# ColourDEV.net
KiCad netlist of a schematic drawn in EAGLE
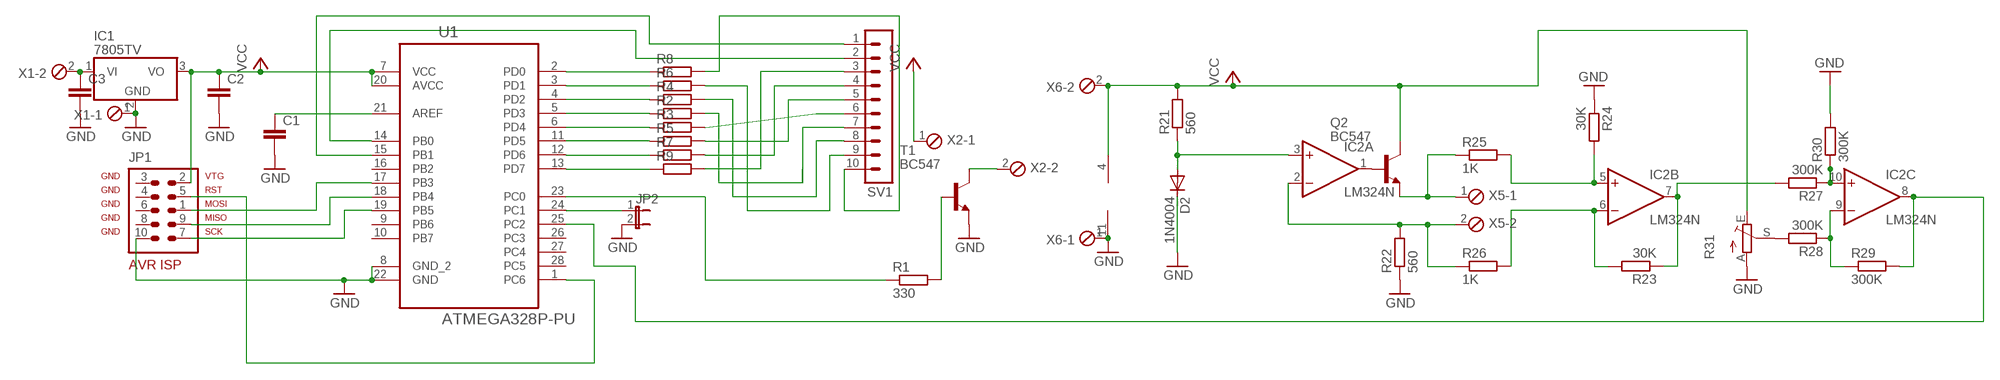
[diagram p0: schematic, sheet 1]

(export (version "E")
  (design (tool "Eeschema 10.0.6"))
  (components
    (comp (ref "C1")
      (value "C-EU050-075X075")
      (footprint "eagle-import:C050-075X075")
      (libsource (lib "eagle-import") (part "C-EU050-075X075"))
    )
    (comp (ref "C2")
      (value "C-EU050-025X075")
      (footprint "eagle-import:C050-025X075")
      (libsource (lib "eagle-import") (part "resistor_348_C-EU050-025X075"))
    )
    (comp (ref "C3")
      (value "C-EU050-025X075")
      (footprint "eagle-import:C050-025X075")
      (libsource (lib "eagle-import") (part "resistor_348_C-EU050-025X075"))
    )
    (comp (ref "D2")
      (value "1N4004")
      (footprint "eagle-import:DO41-10")
      (libsource (lib "eagle-import") (part "1N4004"))
    )
    (comp (ref "IC1")
      (value "7805TV")
      (footprint "eagle-import:TO220V")
      (libsource (lib "eagle-import") (part "78TV05"))
    )
    (comp (ref "IC2")
      (value "LM324N")
      (footprint "eagle-import:DIL14")
      (libsource (lib "eagle-import") (part "LM324N"))
    )
    (comp (ref "JP1")
      (value "AVR-ISP-10")
      (footprint "eagle-import:AVR-ISP-10")
      (libsource (lib "eagle-import") (part "AVR-ISP-10"))
    )
    (comp (ref "JP2")
      (value "JP1E")
      (footprint "eagle-import:JP1")
      (libsource (lib "eagle-import") (part "JP1E"))
    )
    (comp (ref "Q2")
      (value "BC547")
      (footprint "eagle-import:TO92")
      (libsource (lib "eagle-import") (part "BC547"))
    )
    (comp (ref "R1")
      (value "330")
      (footprint "eagle-import:M1206")
      (libsource (lib "eagle-import") (part "resistor_348_R-EU_M1206"))
    )
    (comp (ref "R2")
      (value "R-EU_M1206")
      (footprint "eagle-import:M1206")
      (libsource (lib "eagle-import") (part "resistor_348_R-EU_M1206"))
    )
    (comp (ref "R3")
      (value "R-EU_M1206")
      (footprint "eagle-import:M1206")
      (libsource (lib "eagle-import") (part "resistor_348_R-EU_M1206"))
    )
    (comp (ref "R4")
      (value "R-EU_M1206")
      (footprint "eagle-import:M1206")
      (libsource (lib "eagle-import") (part "resistor_348_R-EU_M1206"))
    )
    (comp (ref "R5")
      (value "R-EU_M1206")
      (footprint "eagle-import:M1206")
      (libsource (lib "eagle-import") (part "resistor_348_R-EU_M1206"))
    )
    (comp (ref "R6")
      (value "R-EU_M1206")
      (footprint "eagle-import:M1206")
      (libsource (lib "eagle-import") (part "resistor_348_R-EU_M1206"))
    )
    (comp (ref "R7")
      (value "R-EU_M1206")
      (footprint "eagle-import:M1206")
      (libsource (lib "eagle-import") (part "resistor_348_R-EU_M1206"))
    )
    (comp (ref "R8")
      (value "R-EU_M1206")
      (footprint "eagle-import:M1206")
      (libsource (lib "eagle-import") (part "resistor_348_R-EU_M1206"))
    )
    (comp (ref "R9")
      (value "R-EU_M1206")
      (footprint "eagle-import:M1206")
      (libsource (lib "eagle-import") (part "resistor_348_R-EU_M1206"))
    )
    (comp (ref "R21")
      (value "560")
      (footprint "eagle-import:M1206")
      (libsource (lib "eagle-import") (part "R-EU_M1206"))
    )
    (comp (ref "R22")
      (value "560")
      (footprint "eagle-import:M1206")
      (libsource (lib "eagle-import") (part "R-EU_M1206"))
    )
    (comp (ref "R23")
      (value "30K")
      (footprint "eagle-import:M1206")
      (libsource (lib "eagle-import") (part "R-EU_M1206"))
    )
    (comp (ref "R24")
      (value "30K")
      (footprint "eagle-import:M1206")
      (libsource (lib "eagle-import") (part "R-EU_M1206"))
    )
    (comp (ref "R25")
      (value "1K")
      (footprint "eagle-import:M1206")
      (libsource (lib "eagle-import") (part "R-EU_M1206"))
    )
    (comp (ref "R26")
      (value "1K")
      (footprint "eagle-import:M1206")
      (libsource (lib "eagle-import") (part "R-EU_M1206"))
    )
    (comp (ref "R27")
      (value "300K")
      (footprint "eagle-import:M1206")
      (libsource (lib "eagle-import") (part "R-EU_M1206"))
    )
    (comp (ref "R28")
      (value "300K")
      (footprint "eagle-import:M1206")
      (libsource (lib "eagle-import") (part "R-EU_M1206"))
    )
    (comp (ref "R29")
      (value "300K")
      (footprint "eagle-import:M1206")
      (libsource (lib "eagle-import") (part "R-EU_M1206"))
    )
    (comp (ref "R30")
      (value "300K")
      (footprint "eagle-import:M1206")
      (libsource (lib "eagle-import") (part "R-EU_M1206"))
    )
    (comp (ref "R31")
      (value "TRIM_EU-LI10")
      (footprint "eagle-import:LI10")
      (libsource (lib "eagle-import") (part "TRIM_EU-LI10"))
    )
    (comp (ref "SV1")
      (value "MA10-1")
      (footprint "eagle-import:MA10-1")
      (libsource (lib "eagle-import") (part "MA10-1"))
    )
    (comp (ref "T1")
      (value "BC547")
      (footprint "eagle-import:TO92")
      (libsource (lib "eagle-import") (part "transistor_402_BC547"))
    )
    (comp (ref "U1")
      (value "ATMEGA328P-PU")
      (footprint "eagle-import:DIP254P762X457-28")
      (libsource (lib "eagle-import") (part "ATMEGA328P-PU"))
    )
    (comp (ref "X1")
      (value "MPT2")
      (footprint "eagle-import:2POL254")
      (libsource (lib "eagle-import") (part "MPT2"))
    )
    (comp (ref "X2")
      (value "MPT2")
      (footprint "eagle-import:2POL254")
      (libsource (lib "eagle-import") (part "MPT2"))
    )
    (comp (ref "X5")
      (value "MPT2")
      (footprint "eagle-import:2POL254")
      (libsource (lib "eagle-import") (part "MPT2"))
    )
    (comp (ref "X6")
      (value "MPT2")
      (footprint "eagle-import:2POL254")
      (libsource (lib "eagle-import") (part "MPT2"))
    )
  )
  (nets
    (net (code "1") (name "GND") (class "Default")
      (node (ref "C1") (pin "2") (pinfunction "2_2") (pintype "passive"))
      (node (ref "C2") (pin "2") (pinfunction "2_2") (pintype "passive"))
      (node (ref "C3") (pin "2") (pinfunction "2_2") (pintype "passive"))
      (node (ref "D2") (pin "C") (pinfunction "C_C") (pintype "passive"))
      (node (ref "IC1") (pin "2") (pinfunction "GND_2") (pintype "passive"))
      (node (ref "IC2") (pin "11") (pinfunction "V-_11") (pintype "power_in"))
      (node (ref "JP1") (pin "10") (pinfunction "10_10") (pintype "passive"))
      (node (ref "JP2") (pin "2") (pinfunction "2_2") (pintype "passive"))
      (node (ref "R22") (pin "1") (pinfunction "1_1") (pintype "passive"))
      (node (ref "R24") (pin "1") (pinfunction "1_1") (pintype "passive"))
      (node (ref "R30") (pin "2") (pinfunction "2_2") (pintype "passive"))
      (node (ref "R31") (pin "A") (pinfunction "A_A") (pintype "passive"))
      (node (ref "T1") (pin "1") (pinfunction "E_1") (pintype "passive"))
      (node (ref "U1") (pin "22") (pinfunction "GND_22") (pintype "passive"))
      (node (ref "U1") (pin "8") (pinfunction "GND_2_8") (pintype "passive"))
      (node (ref "X1") (pin "1") (pinfunction "1_1") (pintype "passive"))
      (node (ref "X6") (pin "1") (pinfunction "1_1") (pintype "passive"))
    )
    (net (code "2") (name "Net-(IC1-VI)") (class "Default")
      (node (ref "C3") (pin "1") (pinfunction "1_1") (pintype "passive"))
      (node (ref "IC1") (pin "1") (pinfunction "VI_1") (pintype "input"))
      (node (ref "X1") (pin "2") (pinfunction "1_2") (pintype "passive"))
    )
    (net (code "3") (name "Net-(IC2A-+IN)") (class "Default")
      (node (ref "D2") (pin "A") (pinfunction "A_A") (pintype "passive"))
      (node (ref "IC2") (pin "3") (pinfunction "+IN_3") (pintype "input"))
      (node (ref "R21") (pin "1") (pinfunction "1_1") (pintype "passive"))
    )
    (net (code "4") (name "Net-(IC2A--IN)") (class "Default")
      (node (ref "IC2") (pin "2") (pinfunction "-IN_2") (pintype "input"))
      (node (ref "R22") (pin "2") (pinfunction "2_2") (pintype "passive"))
      (node (ref "R26") (pin "1") (pinfunction "1_1") (pintype "passive"))
      (node (ref "X5") (pin "2") (pinfunction "1_2") (pintype "passive"))
    )
    (net (code "5") (name "Net-(IC2A-OUT)") (class "Default")
      (node (ref "IC2") (pin "1") (pinfunction "OUT_1") (pintype "output"))
      (node (ref "Q2") (pin "2") (pinfunction "B_2") (pintype "passive"))
    )
    (net (code "6") (name "Net-(IC2B-+IN)") (class "Default")
      (node (ref "IC2") (pin "5") (pinfunction "+IN_5") (pintype "input"))
      (node (ref "R24") (pin "2") (pinfunction "2_2") (pintype "passive"))
      (node (ref "R25") (pin "2") (pinfunction "2_2") (pintype "passive"))
    )
    (net (code "7") (name "Net-(IC2B--IN)") (class "Default")
      (node (ref "IC2") (pin "6") (pinfunction "-IN_6") (pintype "input"))
      (node (ref "R23") (pin "2") (pinfunction "2_2") (pintype "passive"))
      (node (ref "R26") (pin "2") (pinfunction "2_2") (pintype "passive"))
    )
    (net (code "8") (name "Net-(IC2B-OUT)") (class "Default")
      (node (ref "IC2") (pin "7") (pinfunction "OUT_7") (pintype "output"))
      (node (ref "R23") (pin "1") (pinfunction "1_1") (pintype "passive"))
      (node (ref "R27") (pin "2") (pinfunction "2_2") (pintype "passive"))
    )
    (net (code "9") (name "Net-(IC2C-+IN)") (class "Default")
      (node (ref "IC2") (pin "10") (pinfunction "+IN_10") (pintype "input"))
      (node (ref "R27") (pin "1") (pinfunction "1_1") (pintype "passive"))
      (node (ref "R30") (pin "1") (pinfunction "1_1") (pintype "passive"))
    )
    (net (code "10") (name "Net-(IC2C--IN)") (class "Default")
      (node (ref "IC2") (pin "9") (pinfunction "-IN_9") (pintype "input"))
      (node (ref "R28") (pin "1") (pinfunction "1_1") (pintype "passive"))
      (node (ref "R29") (pin "1") (pinfunction "1_1") (pintype "passive"))
    )
    (net (code "11") (name "Net-(IC2C-OUT)") (class "Default")
      (node (ref "IC2") (pin "8") (pinfunction "OUT_8") (pintype "output"))
      (node (ref "R29") (pin "2") (pinfunction "2_2") (pintype "passive"))
      (node (ref "U1") (pin "25") (pinfunction "PC2_25") (pintype "bidirectional"))
    )
    (net (code "12") (name "Net-(Q2-E)") (class "Default")
      (node (ref "Q2") (pin "1") (pinfunction "E_1") (pintype "passive"))
      (node (ref "R25") (pin "1") (pinfunction "1_1") (pintype "passive"))
      (node (ref "X5") (pin "1") (pinfunction "1_1") (pintype "passive"))
    )
    (net (code "13") (name "Net-(R2-Pad2)") (class "Default")
      (node (ref "R2") (pin "2") (pinfunction "2_2") (pintype "passive"))
      (node (ref "SV1") (pin "7") (pinfunction "7_7") (pintype "passive"))
    )
    (net (code "14") (name "Net-(R3-Pad2)") (class "Default")
      (node (ref "R3") (pin "2") (pinfunction "2_2") (pintype "passive"))
      (node (ref "SV1") (pin "6") (pinfunction "6_6") (pintype "passive"))
    )
    (net (code "15") (name "Net-(R4-Pad2)") (class "Default")
      (node (ref "R4") (pin "2") (pinfunction "2_2") (pintype "passive"))
      (node (ref "SV1") (pin "8") (pinfunction "8_8") (pintype "passive"))
    )
    (net (code "16") (name "Net-(R5-Pad2)") (class "Default")
      (node (ref "R5") (pin "2") (pinfunction "2_2") (pintype "passive"))
      (node (ref "SV1") (pin "5") (pinfunction "5_5") (pintype "passive"))
    )
    (net (code "17") (name "Net-(R6-Pad2)") (class "Default")
      (node (ref "R6") (pin "2") (pinfunction "2_2") (pintype "passive"))
      (node (ref "SV1") (pin "9") (pinfunction "9_9") (pintype "passive"))
    )
    (net (code "18") (name "Net-(R7-Pad2)") (class "Default")
      (node (ref "R7") (pin "2") (pinfunction "2_2") (pintype "passive"))
      (node (ref "SV1") (pin "4") (pinfunction "4_4") (pintype "passive"))
    )
    (net (code "19") (name "Net-(R8-Pad2)") (class "Default")
      (node (ref "R8") (pin "2") (pinfunction "2_2") (pintype "passive"))
      (node (ref "SV1") (pin "10") (pinfunction "10_10") (pintype "passive"))
    )
    (net (code "20") (name "Net-(R9-Pad2)") (class "Default")
      (node (ref "R9") (pin "2") (pinfunction "2_2") (pintype "passive"))
      (node (ref "SV1") (pin "3") (pinfunction "3_3") (pintype "passive"))
    )
    (net (code "21") (name "Net-(R28-Pad2)") (class "Default")
      (node (ref "R28") (pin "2") (pinfunction "2_2") (pintype "passive"))
      (node (ref "R31") (pin "S") (pinfunction "S_S") (pintype "passive"))
    )
    (net (code "22") (name "Net-(T1-B)") (class "Default")
      (node (ref "R1") (pin "2") (pinfunction "2_2") (pintype "passive"))
      (node (ref "T1") (pin "2") (pinfunction "B_2") (pintype "passive"))
    )
    (net (code "23") (name "Net-(T1-C)") (class "Default")
      (node (ref "T1") (pin "3") (pinfunction "C_3") (pintype "passive"))
      (node (ref "X2") (pin "2") (pinfunction "1_2") (pintype "passive"))
    )
    (net (code "24") (name "Net-(U1-AREF)") (class "Default")
      (node (ref "C1") (pin "1") (pinfunction "1_1") (pintype "passive"))
      (node (ref "U1") (pin "21") (pinfunction "AREF_21") (pintype "input"))
    )
    (net (code "25") (name "Net-(U1-PB0)") (class "Default")
      (node (ref "SV1") (pin "2") (pinfunction "2_2") (pintype "passive"))
      (node (ref "U1") (pin "14") (pinfunction "PB0_14") (pintype "bidirectional"))
    )
    (net (code "26") (name "Net-(U1-PB1)") (class "Default")
      (node (ref "SV1") (pin "1") (pinfunction "1_1") (pintype "passive"))
      (node (ref "U1") (pin "15") (pinfunction "PB1_15") (pintype "bidirectional"))
    )
    (net (code "27") (name "Net-(U1-PB3)") (class "Default")
      (node (ref "JP1") (pin "1") (pinfunction "1_1") (pintype "passive"))
      (node (ref "U1") (pin "17") (pinfunction "PB3_17") (pintype "bidirectional"))
    )
    (net (code "28") (name "Net-(U1-PB4)") (class "Default")
      (node (ref "JP1") (pin "9") (pinfunction "9_9") (pintype "passive"))
      (node (ref "U1") (pin "18") (pinfunction "PB4_18") (pintype "bidirectional"))
    )
    (net (code "29") (name "Net-(U1-PB5)") (class "Default")
      (node (ref "JP1") (pin "7") (pinfunction "7_7") (pintype "passive"))
      (node (ref "U1") (pin "19") (pinfunction "PB5_19") (pintype "bidirectional"))
    )
    (net (code "30") (name "Net-(U1-PC0)") (class "Default")
      (node (ref "R1") (pin "1") (pinfunction "1_1") (pintype "passive"))
      (node (ref "U1") (pin "23") (pinfunction "PC0_23") (pintype "bidirectional"))
    )
    (net (code "31") (name "Net-(U1-PC1)") (class "Default")
      (node (ref "JP2") (pin "1") (pinfunction "1_1") (pintype "passive"))
      (node (ref "U1") (pin "24") (pinfunction "PC1_24") (pintype "bidirectional"))
    )
    (net (code "32") (name "Net-(U1-PC6)") (class "Default")
      (node (ref "JP1") (pin "5") (pinfunction "5_5") (pintype "passive"))
      (node (ref "U1") (pin "1") (pinfunction "PC6_1") (pintype "bidirectional"))
    )
    (net (code "33") (name "Net-(U1-PD0)") (class "Default")
      (node (ref "R8") (pin "1") (pinfunction "1_1") (pintype "passive"))
      (node (ref "U1") (pin "2") (pinfunction "PD0_2") (pintype "bidirectional"))
    )
    (net (code "34") (name "Net-(U1-PD1)") (class "Default")
      (node (ref "R6") (pin "1") (pinfunction "1_1") (pintype "passive"))
      (node (ref "U1") (pin "3") (pinfunction "PD1_3") (pintype "bidirectional"))
    )
    (net (code "35") (name "Net-(U1-PD2)") (class "Default")
      (node (ref "R4") (pin "1") (pinfunction "1_1") (pintype "passive"))
      (node (ref "U1") (pin "4") (pinfunction "PD2_4") (pintype "bidirectional"))
    )
    (net (code "36") (name "Net-(U1-PD3)") (class "Default")
      (node (ref "R2") (pin "1") (pinfunction "1_1") (pintype "passive"))
      (node (ref "U1") (pin "5") (pinfunction "PD3_5") (pintype "bidirectional"))
    )
    (net (code "37") (name "Net-(U1-PD4)") (class "Default")
      (node (ref "R3") (pin "1") (pinfunction "1_1") (pintype "passive"))
      (node (ref "U1") (pin "6") (pinfunction "PD4_6") (pintype "bidirectional"))
    )
    (net (code "38") (name "Net-(U1-PD5)") (class "Default")
      (node (ref "R5") (pin "1") (pinfunction "1_1") (pintype "passive"))
      (node (ref "U1") (pin "11") (pinfunction "PD5_11") (pintype "bidirectional"))
    )
    (net (code "39") (name "Net-(U1-PD6)") (class "Default")
      (node (ref "R7") (pin "1") (pinfunction "1_1") (pintype "passive"))
      (node (ref "U1") (pin "12") (pinfunction "PD6_12") (pintype "bidirectional"))
    )
    (net (code "40") (name "Net-(U1-PD7)") (class "Default")
      (node (ref "R9") (pin "1") (pinfunction "1_1") (pintype "passive"))
      (node (ref "U1") (pin "13") (pinfunction "PD7_13") (pintype "bidirectional"))
    )
    (net (code "41") (name "VCC") (class "Default")
      (node (ref "C2") (pin "1") (pinfunction "1_1") (pintype "passive"))
      (node (ref "IC1") (pin "3") (pinfunction "VO_3") (pintype "passive"))
      (node (ref "IC2") (pin "4") (pinfunction "V+_4") (pintype "power_in"))
      (node (ref "JP1") (pin "2") (pinfunction "2_2") (pintype "passive"))
      (node (ref "Q2") (pin "3") (pinfunction "C_3") (pintype "passive"))
      (node (ref "R21") (pin "2") (pinfunction "2_2") (pintype "passive"))
      (node (ref "R31") (pin "E") (pinfunction "E_E") (pintype "passive"))
      (node (ref "U1") (pin "20") (pinfunction "AVCC_20") (pintype "power_in"))
      (node (ref "U1") (pin "7") (pinfunction "VCC_7") (pintype "power_in"))
      (node (ref "X2") (pin "1") (pinfunction "1_1") (pintype "passive"))
      (node (ref "X6") (pin "2") (pinfunction "1_2") (pintype "passive"))
    )
    (net (code "42") (name "unconnected-(JP1-Pad3)") (class "Default")
      (node (ref "JP1") (pin "3") (pinfunction "3_3") (pintype "passive"))
    )
    (net (code "43") (name "unconnected-(JP1-Pad4)") (class "Default")
      (node (ref "JP1") (pin "4") (pinfunction "4_4") (pintype "passive"))
    )
    (net (code "44") (name "unconnected-(JP1-Pad6)") (class "Default")
      (node (ref "JP1") (pin "6") (pinfunction "6_6") (pintype "passive"))
    )
    (net (code "45") (name "unconnected-(JP1-Pad8)") (class "Default")
      (node (ref "JP1") (pin "8") (pinfunction "8_8") (pintype "passive"))
    )
    (net (code "46") (name "unconnected-(U1-PB2-Pad16)") (class "Default")
      (node (ref "U1") (pin "16") (pinfunction "PB2_16") (pintype "bidirectional"))
    )
    (net (code "47") (name "unconnected-(U1-PB6-Pad9)") (class "Default")
      (node (ref "U1") (pin "9") (pinfunction "PB6_9") (pintype "bidirectional"))
    )
    (net (code "48") (name "unconnected-(U1-PB7-Pad10)") (class "Default")
      (node (ref "U1") (pin "10") (pinfunction "PB7_10") (pintype "bidirectional"))
    )
    (net (code "49") (name "unconnected-(U1-PC3-Pad26)") (class "Default")
      (node (ref "U1") (pin "26") (pinfunction "PC3_26") (pintype "bidirectional"))
    )
    (net (code "50") (name "unconnected-(U1-PC4-Pad27)") (class "Default")
      (node (ref "U1") (pin "27") (pinfunction "PC4_27") (pintype "bidirectional"))
    )
    (net (code "51") (name "unconnected-(U1-PC5-Pad28)") (class "Default")
      (node (ref "U1") (pin "28") (pinfunction "PC5_28") (pintype "bidirectional"))
    )
  )
)
